# FPGA_interface.net
KiCad netlist of a schematic drawn in Altium Designer
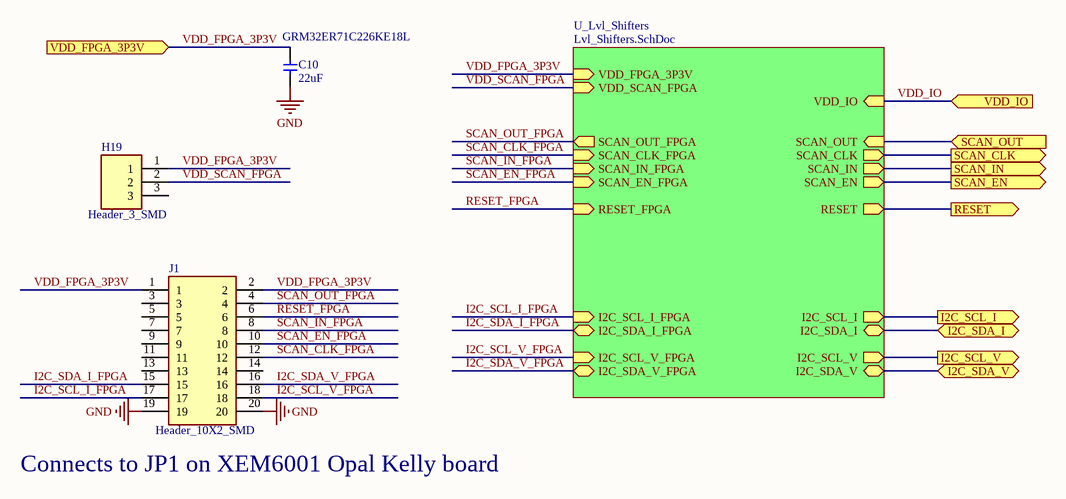
[diagram p0: FPGA_interface.SchDoc]

(export (version "E")
  (design (tool "Eeschema 10.0.6"))
  (components
    (comp (ref "C10")
      (value "22uF")
      (footprint "CAPC3225X27N")
      (description "CAP CER 22uF 10% 16V X7R 1210")
      (fields
        (field (name "MANUFACTURER") "Murata")
        (field (name "SUPPLIER PART NUMBER 1") "GRM32ER71C226KE18L")
      )
      (libsource (lib "fader2_parts") (part "cap 22uF"))
    )
    (comp (ref "H19")
      (value "Header_3_SMD")
      (footprint "HDR1X3_SMD")
      (description "Connector Header Vertical, SMD, 3 position 0.100\" (2.54mm)")
      (fields
        (field (name "MANUFACTURER_PART_NUMBER") "TSM-103-01-S-SV-P-TR")
        (field (name "MOUSER PART NUMBER") "200-TSM10301SSVPTR")
      )
      (libsource (lib "fader2_parts") (part "Header_3_SMD"))
    )
    (comp (ref "J1")
      (value "Header_10X2_SMD")
      (footprint "HDR2X10_SMD")
      (description "Connector Header Vertical Dual Row, SMD, 20 position 0.100\" (2.54mm)")
      (fields
        (field (name "MANUFACTURER_PART_NUMBER") "TSM-110-01-L-DV-P-TR")
        (field (name "MOUSER PART NUMBER") "200-TSM11001LDVPTR")
      )
      (libsource (lib "fader2_parts") (part "Header_10X2_SMD"))
    )
  )
  (nets
    (net (code "2") (name "/I2C_SCL_I_FPGA") (class "Default")
      (node (ref "J1") (pin "17") (pinfunction "17_17") (pintype "passive"))
    )
    (net (code "4") (name "/I2C_SCL_V_FPGA") (class "Default")
      (node (ref "J1") (pin "18") (pinfunction "18_18") (pintype "passive"))
    )
    (net (code "6") (name "/I2C_SDA_I_FPGA") (class "Default")
      (node (ref "J1") (pin "15") (pinfunction "15_15") (pintype "passive"))
    )
    (net (code "8") (name "/I2C_SDA_V_FPGA") (class "Default")
      (node (ref "J1") (pin "16") (pinfunction "16_16") (pintype "passive"))
    )
    (net (code "10") (name "/RESET_FPGA") (class "Default")
      (node (ref "J1") (pin "6") (pinfunction "6_6") (pintype "passive"))
    )
    (net (code "12") (name "/SCAN_CLK_FPGA") (class "Default")
      (node (ref "J1") (pin "12") (pinfunction "12_12") (pintype "passive"))
    )
    (net (code "14") (name "/SCAN_EN_FPGA") (class "Default")
      (node (ref "J1") (pin "10") (pinfunction "10_10") (pintype "passive"))
    )
    (net (code "16") (name "/SCAN_IN_FPGA") (class "Default")
      (node (ref "J1") (pin "8") (pinfunction "8_8") (pintype "passive"))
    )
    (net (code "18") (name "/SCAN_OUT_FPGA") (class "Default")
      (node (ref "J1") (pin "4") (pinfunction "4_4") (pintype "passive"))
    )
    (net (code "19") (name "/VDD_FPGA_3P3V") (class "Default")
      (node (ref "C10") (pin "1") (pinfunction "1_1") (pintype "passive"))
      (node (ref "H19") (pin "1") (pinfunction "1_1") (pintype "passive"))
      (node (ref "J1") (pin "1") (pinfunction "1_1") (pintype "passive"))
      (node (ref "J1") (pin "2") (pinfunction "2_2") (pintype "passive"))
    )
    (net (code "21") (name "/VDD_SCAN_FPGA") (class "Default")
      (node (ref "H19") (pin "2") (pinfunction "2_2") (pintype "passive"))
    )
    (net (code "22") (name "GND") (class "Default")
      (node (ref "C10") (pin "2") (pinfunction "2_2") (pintype "passive"))
      (node (ref "J1") (pin "19") (pinfunction "19_19") (pintype "passive"))
      (node (ref "J1") (pin "20") (pinfunction "20_20") (pintype "passive"))
    )
    (net (code "23") (name "unconnected-(H19-Pad3)") (class "Default")
      (node (ref "H19") (pin "3") (pinfunction "3_3") (pintype "passive"))
    )
    (net (code "24") (name "unconnected-(J1-Pad3)") (class "Default")
      (node (ref "J1") (pin "3") (pinfunction "3_3") (pintype "passive"))
    )
    (net (code "25") (name "unconnected-(J1-Pad5)") (class "Default")
      (node (ref "J1") (pin "5") (pinfunction "5_5") (pintype "passive"))
    )
    (net (code "26") (name "unconnected-(J1-Pad7)") (class "Default")
      (node (ref "J1") (pin "7") (pinfunction "7_7") (pintype "passive"))
    )
    (net (code "27") (name "unconnected-(J1-Pad9)") (class "Default")
      (node (ref "J1") (pin "9") (pinfunction "9_9") (pintype "passive"))
    )
    (net (code "28") (name "unconnected-(J1-Pad11)") (class "Default")
      (node (ref "J1") (pin "11") (pinfunction "11_11") (pintype "passive"))
    )
    (net (code "29") (name "unconnected-(J1-Pad13)") (class "Default")
      (node (ref "J1") (pin "13") (pinfunction "13_13") (pintype "passive"))
    )
    (net (code "30") (name "unconnected-(J1-Pad14)") (class "Default")
      (node (ref "J1") (pin "14") (pinfunction "14_14") (pintype "passive"))
    )
  )
)
